# Sensor_LF_V_2C.net
KiCad netlist of a schematic drawn in EAGLE
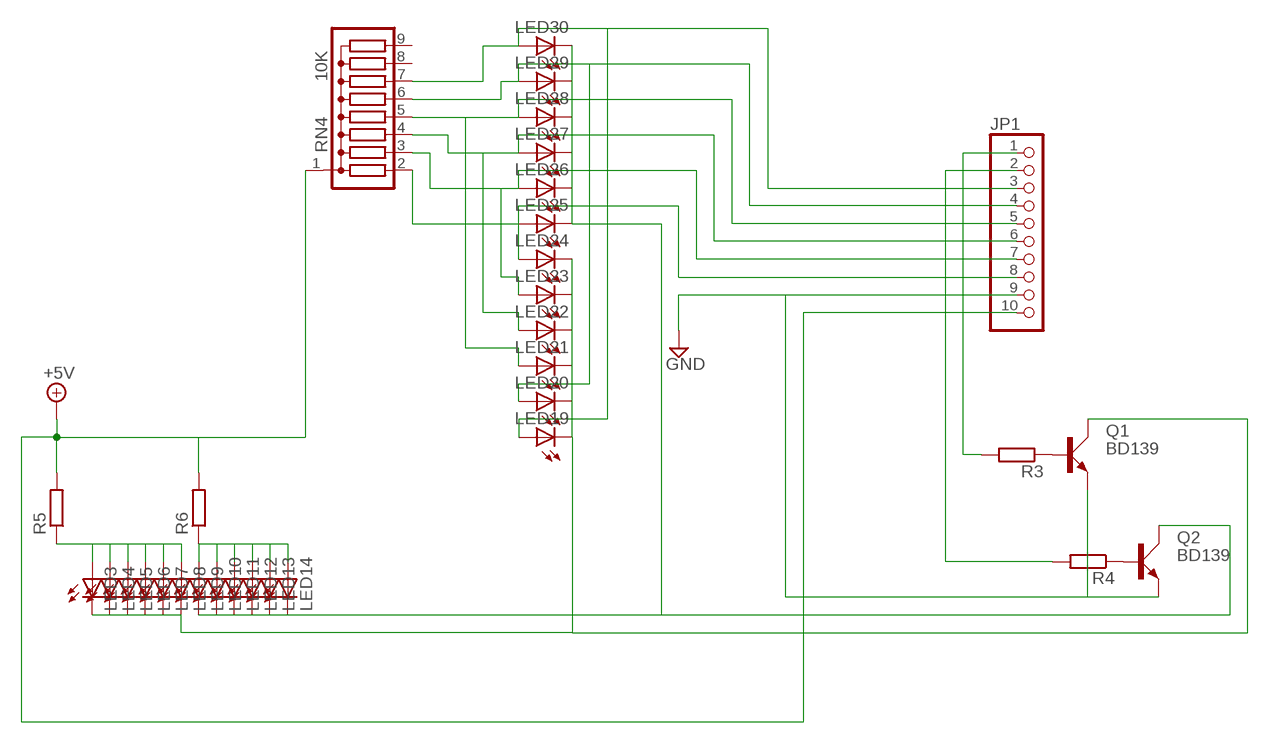
[diagram p0: schematic, sheet 1]

(export (version "E")
  (design (tool "Eeschema 10.0.6"))
  (components
    (comp (ref "JP1")
      (value "PINHD-1X10")
      (footprint "eagle-import:1X10")
      (libsource (lib "eagle-import") (part "PINHD-1X10"))
    )
    (comp (ref "LED3")
      (value "LED3MM")
      (footprint "eagle-import:LED3MM")
      (libsource (lib "eagle-import") (part "LED3MM"))
    )
    (comp (ref "LED4")
      (value "LED3MM")
      (footprint "eagle-import:LED3MM")
      (libsource (lib "eagle-import") (part "LED3MM"))
    )
    (comp (ref "LED5")
      (value "LED3MM")
      (footprint "eagle-import:LED3MM")
      (libsource (lib "eagle-import") (part "LED3MM"))
    )
    (comp (ref "LED6")
      (value "LED3MM")
      (footprint "eagle-import:LED3MM")
      (libsource (lib "eagle-import") (part "LED3MM"))
    )
    (comp (ref "LED7")
      (value "LED3MM")
      (footprint "eagle-import:LED3MM")
      (libsource (lib "eagle-import") (part "LED3MM"))
    )
    (comp (ref "LED8")
      (value "LED3MM")
      (footprint "eagle-import:LED3MM")
      (libsource (lib "eagle-import") (part "LED3MM"))
    )
    (comp (ref "LED9")
      (value "LED3MM")
      (footprint "eagle-import:LED3MM")
      (libsource (lib "eagle-import") (part "LED3MM"))
    )
    (comp (ref "LED10")
      (value "LED3MM")
      (footprint "eagle-import:LED3MM")
      (libsource (lib "eagle-import") (part "LED3MM"))
    )
    (comp (ref "LED11")
      (value "LED3MM")
      (footprint "eagle-import:LED3MM")
      (libsource (lib "eagle-import") (part "LED3MM"))
    )
    (comp (ref "LED12")
      (value "LED3MM")
      (footprint "eagle-import:LED3MM")
      (libsource (lib "eagle-import") (part "LED3MM"))
    )
    (comp (ref "LED13")
      (value "LED3MM")
      (footprint "eagle-import:LED3MM")
      (libsource (lib "eagle-import") (part "LED3MM"))
    )
    (comp (ref "LED14")
      (value "LED3MM")
      (footprint "eagle-import:LED3MM")
      (libsource (lib "eagle-import") (part "LED3MM"))
    )
    (comp (ref "LED19")
      (value "LED3MM")
      (footprint "eagle-import:LED3MM")
      (libsource (lib "eagle-import") (part "LED3MM"))
    )
    (comp (ref "LED20")
      (value "LED3MM")
      (footprint "eagle-import:LED3MM")
      (libsource (lib "eagle-import") (part "LED3MM"))
    )
    (comp (ref "LED21")
      (value "LED3MM")
      (footprint "eagle-import:LED3MM")
      (libsource (lib "eagle-import") (part "LED3MM"))
    )
    (comp (ref "LED22")
      (value "LED3MM")
      (footprint "eagle-import:LED3MM")
      (libsource (lib "eagle-import") (part "LED3MM"))
    )
    (comp (ref "LED23")
      (value "LED3MM")
      (footprint "eagle-import:LED3MM")
      (libsource (lib "eagle-import") (part "LED3MM"))
    )
    (comp (ref "LED24")
      (value "LED3MM")
      (footprint "eagle-import:LED3MM")
      (libsource (lib "eagle-import") (part "LED3MM"))
    )
    (comp (ref "LED25")
      (value "LED3MM")
      (footprint "eagle-import:LED3MM")
      (libsource (lib "eagle-import") (part "LED3MM"))
    )
    (comp (ref "LED26")
      (value "LED3MM")
      (footprint "eagle-import:LED3MM")
      (libsource (lib "eagle-import") (part "LED3MM"))
    )
    (comp (ref "LED27")
      (value "LED3MM")
      (footprint "eagle-import:LED3MM")
      (libsource (lib "eagle-import") (part "LED3MM"))
    )
    (comp (ref "LED28")
      (value "LED3MM")
      (footprint "eagle-import:LED3MM")
      (libsource (lib "eagle-import") (part "LED3MM"))
    )
    (comp (ref "LED29")
      (value "LED3MM")
      (footprint "eagle-import:LED3MM")
      (libsource (lib "eagle-import") (part "LED3MM"))
    )
    (comp (ref "LED30")
      (value "LED3MM")
      (footprint "eagle-import:LED3MM")
      (libsource (lib "eagle-import") (part "LED3MM"))
    )
    (comp (ref "Q1")
      (value "BD139")
      (footprint "eagle-import:TO126AV")
      (libsource (lib "eagle-import") (part "BD139"))
    )
    (comp (ref "Q2")
      (value "BD139")
      (footprint "eagle-import:TO126AV")
      (libsource (lib "eagle-import") (part "BD139"))
    )
    (comp (ref "R3")
      (value "R-EU_0204/7")
      (footprint "eagle-import:0204_7")
      (libsource (lib "eagle-import") (part "R-EU_0204/7"))
    )
    (comp (ref "R4")
      (value "R-EU_0204/7")
      (footprint "eagle-import:0204_7")
      (libsource (lib "eagle-import") (part "R-EU_0204/7"))
    )
    (comp (ref "R5")
      (value "R-EU_0204/7")
      (footprint "eagle-import:0204_7")
      (libsource (lib "eagle-import") (part "R-EU_0204/7"))
    )
    (comp (ref "R6")
      (value "R-EU_0204/7")
      (footprint "eagle-import:0204_7")
      (libsource (lib "eagle-import") (part "R-EU_0204/7"))
    )
    (comp (ref "RN4")
      (value "10K")
      (footprint "eagle-import:SIL9")
      (libsource (lib "eagle-import") (part "G08R"))
    )
  )
  (nets
    (net (code "1") (name "+5V") (class "Default")
      (node (ref "JP1") (pin "10") (pinfunction "10_10") (pintype "passive"))
      (node (ref "R5") (pin "2") (pinfunction "2_2") (pintype "passive"))
      (node (ref "R6") (pin "2") (pinfunction "2_2") (pintype "passive"))
      (node (ref "RN4") (pin "1") (pinfunction "1_1") (pintype "passive"))
    )
    (net (code "2") (name "GND") (class "Default")
      (node (ref "JP1") (pin "9") (pinfunction "9_9") (pintype "passive"))
      (node (ref "Q1") (pin "E") (pinfunction "E_E") (pintype "passive"))
      (node (ref "Q2") (pin "E") (pinfunction "E_E") (pintype "passive"))
    )
    (net (code "3") (name "Net-(JP1-Pad1)") (class "Default")
      (node (ref "JP1") (pin "1") (pinfunction "1_1") (pintype "passive"))
      (node (ref "R3") (pin "2") (pinfunction "2_2") (pintype "passive"))
    )
    (net (code "4") (name "Net-(JP1-Pad2)") (class "Default")
      (node (ref "JP1") (pin "2") (pinfunction "2_2") (pintype "passive"))
      (node (ref "R4") (pin "2") (pinfunction "2_2") (pintype "passive"))
    )
    (net (code "5") (name "Net-(JP1-Pad3)") (class "Default")
      (node (ref "JP1") (pin "3") (pinfunction "3_3") (pintype "passive"))
      (node (ref "LED19") (pin "A") (pinfunction "A_A") (pintype "passive"))
      (node (ref "LED30") (pin "A") (pinfunction "A_A") (pintype "passive"))
      (node (ref "RN4") (pin "7") (pinfunction "7_7") (pintype "passive"))
    )
    (net (code "6") (name "Net-(JP1-Pad4)") (class "Default")
      (node (ref "JP1") (pin "4") (pinfunction "4_4") (pintype "passive"))
      (node (ref "LED20") (pin "A") (pinfunction "A_A") (pintype "passive"))
      (node (ref "LED29") (pin "A") (pinfunction "A_A") (pintype "passive"))
      (node (ref "RN4") (pin "6") (pinfunction "6_6") (pintype "passive"))
    )
    (net (code "7") (name "Net-(JP1-Pad5)") (class "Default")
      (node (ref "JP1") (pin "5") (pinfunction "5_5") (pintype "passive"))
      (node (ref "LED21") (pin "A") (pinfunction "A_A") (pintype "passive"))
      (node (ref "LED28") (pin "A") (pinfunction "A_A") (pintype "passive"))
      (node (ref "RN4") (pin "5") (pinfunction "5_5") (pintype "passive"))
    )
    (net (code "8") (name "Net-(JP1-Pad6)") (class "Default")
      (node (ref "JP1") (pin "6") (pinfunction "6_6") (pintype "passive"))
      (node (ref "LED22") (pin "A") (pinfunction "A_A") (pintype "passive"))
      (node (ref "LED27") (pin "A") (pinfunction "A_A") (pintype "passive"))
      (node (ref "RN4") (pin "4") (pinfunction "4_4") (pintype "passive"))
    )
    (net (code "9") (name "Net-(JP1-Pad7)") (class "Default")
      (node (ref "JP1") (pin "7") (pinfunction "7_7") (pintype "passive"))
      (node (ref "LED23") (pin "A") (pinfunction "A_A") (pintype "passive"))
      (node (ref "LED26") (pin "A") (pinfunction "A_A") (pintype "passive"))
      (node (ref "RN4") (pin "3") (pinfunction "3_3") (pintype "passive"))
    )
    (net (code "10") (name "Net-(JP1-Pad8)") (class "Default")
      (node (ref "JP1") (pin "8") (pinfunction "8_8") (pintype "passive"))
      (node (ref "LED24") (pin "A") (pinfunction "A_A") (pintype "passive"))
      (node (ref "LED25") (pin "A") (pinfunction "A_A") (pintype "passive"))
      (node (ref "RN4") (pin "2") (pinfunction "2_2") (pintype "passive"))
    )
    (net (code "11") (name "Net-(LED3-PadA)") (class "Default")
      (node (ref "LED3") (pin "A") (pinfunction "A_A") (pintype "passive"))
      (node (ref "LED4") (pin "A") (pinfunction "A_A") (pintype "passive"))
      (node (ref "LED5") (pin "A") (pinfunction "A_A") (pintype "passive"))
      (node (ref "LED6") (pin "A") (pinfunction "A_A") (pintype "passive"))
      (node (ref "LED7") (pin "A") (pinfunction "A_A") (pintype "passive"))
      (node (ref "LED8") (pin "A") (pinfunction "A_A") (pintype "passive"))
      (node (ref "R5") (pin "1") (pinfunction "1_1") (pintype "passive"))
    )
    (net (code "12") (name "Net-(LED10-C)") (class "Default")
      (node (ref "LED10") (pin "K") (pinfunction "C_K") (pintype "passive"))
      (node (ref "LED11") (pin "K") (pinfunction "C_K") (pintype "passive"))
      (node (ref "LED12") (pin "K") (pinfunction "C_K") (pintype "passive"))
      (node (ref "LED13") (pin "K") (pinfunction "C_K") (pintype "passive"))
      (node (ref "LED14") (pin "K") (pinfunction "C_K") (pintype "passive"))
      (node (ref "LED25") (pin "K") (pinfunction "C_K") (pintype "passive"))
      (node (ref "LED26") (pin "K") (pinfunction "C_K") (pintype "passive"))
      (node (ref "LED27") (pin "K") (pinfunction "C_K") (pintype "passive"))
      (node (ref "LED28") (pin "K") (pinfunction "C_K") (pintype "passive"))
      (node (ref "LED29") (pin "K") (pinfunction "C_K") (pintype "passive"))
      (node (ref "LED30") (pin "K") (pinfunction "C_K") (pintype "passive"))
      (node (ref "LED9") (pin "K") (pinfunction "C_K") (pintype "passive"))
      (node (ref "Q2") (pin "C") (pinfunction "C_C") (pintype "passive"))
    )
    (net (code "13") (name "Net-(LED10-PadA)") (class "Default")
      (node (ref "LED10") (pin "A") (pinfunction "A_A") (pintype "passive"))
      (node (ref "LED11") (pin "A") (pinfunction "A_A") (pintype "passive"))
      (node (ref "LED12") (pin "A") (pinfunction "A_A") (pintype "passive"))
      (node (ref "LED13") (pin "A") (pinfunction "A_A") (pintype "passive"))
      (node (ref "LED14") (pin "A") (pinfunction "A_A") (pintype "passive"))
      (node (ref "LED9") (pin "A") (pinfunction "A_A") (pintype "passive"))
      (node (ref "R6") (pin "1") (pinfunction "1_1") (pintype "passive"))
    )
    (net (code "14") (name "Net-(LED19-C)") (class "Default")
      (node (ref "LED19") (pin "K") (pinfunction "C_K") (pintype "passive"))
      (node (ref "LED20") (pin "K") (pinfunction "C_K") (pintype "passive"))
      (node (ref "LED21") (pin "K") (pinfunction "C_K") (pintype "passive"))
      (node (ref "LED22") (pin "K") (pinfunction "C_K") (pintype "passive"))
      (node (ref "LED23") (pin "K") (pinfunction "C_K") (pintype "passive"))
      (node (ref "LED24") (pin "K") (pinfunction "C_K") (pintype "passive"))
      (node (ref "LED3") (pin "K") (pinfunction "C_K") (pintype "passive"))
      (node (ref "LED4") (pin "K") (pinfunction "C_K") (pintype "passive"))
      (node (ref "LED5") (pin "K") (pinfunction "C_K") (pintype "passive"))
      (node (ref "LED6") (pin "K") (pinfunction "C_K") (pintype "passive"))
      (node (ref "LED7") (pin "K") (pinfunction "C_K") (pintype "passive"))
      (node (ref "LED8") (pin "K") (pinfunction "C_K") (pintype "passive"))
      (node (ref "Q1") (pin "C") (pinfunction "C_C") (pintype "passive"))
    )
    (net (code "15") (name "Net-(Q1-PadB)") (class "Default")
      (node (ref "Q1") (pin "B") (pinfunction "B_B") (pintype "passive"))
      (node (ref "R3") (pin "1") (pinfunction "1_1") (pintype "passive"))
    )
    (net (code "16") (name "Net-(Q2-PadB)") (class "Default")
      (node (ref "Q2") (pin "B") (pinfunction "B_B") (pintype "passive"))
      (node (ref "R4") (pin "1") (pinfunction "1_1") (pintype "passive"))
    )
    (net (code "17") (name "unconnected-(RN4-Pad8)") (class "Default")
      (node (ref "RN4") (pin "8") (pinfunction "8_8") (pintype "passive"))
    )
    (net (code "18") (name "unconnected-(RN4-Pad9)") (class "Default")
      (node (ref "RN4") (pin "9") (pinfunction "9_9") (pintype "passive"))
    )
  )
)
